# e202var-receiver-v1_1.net
KiCad netlist of a schematic drawn in EAGLE
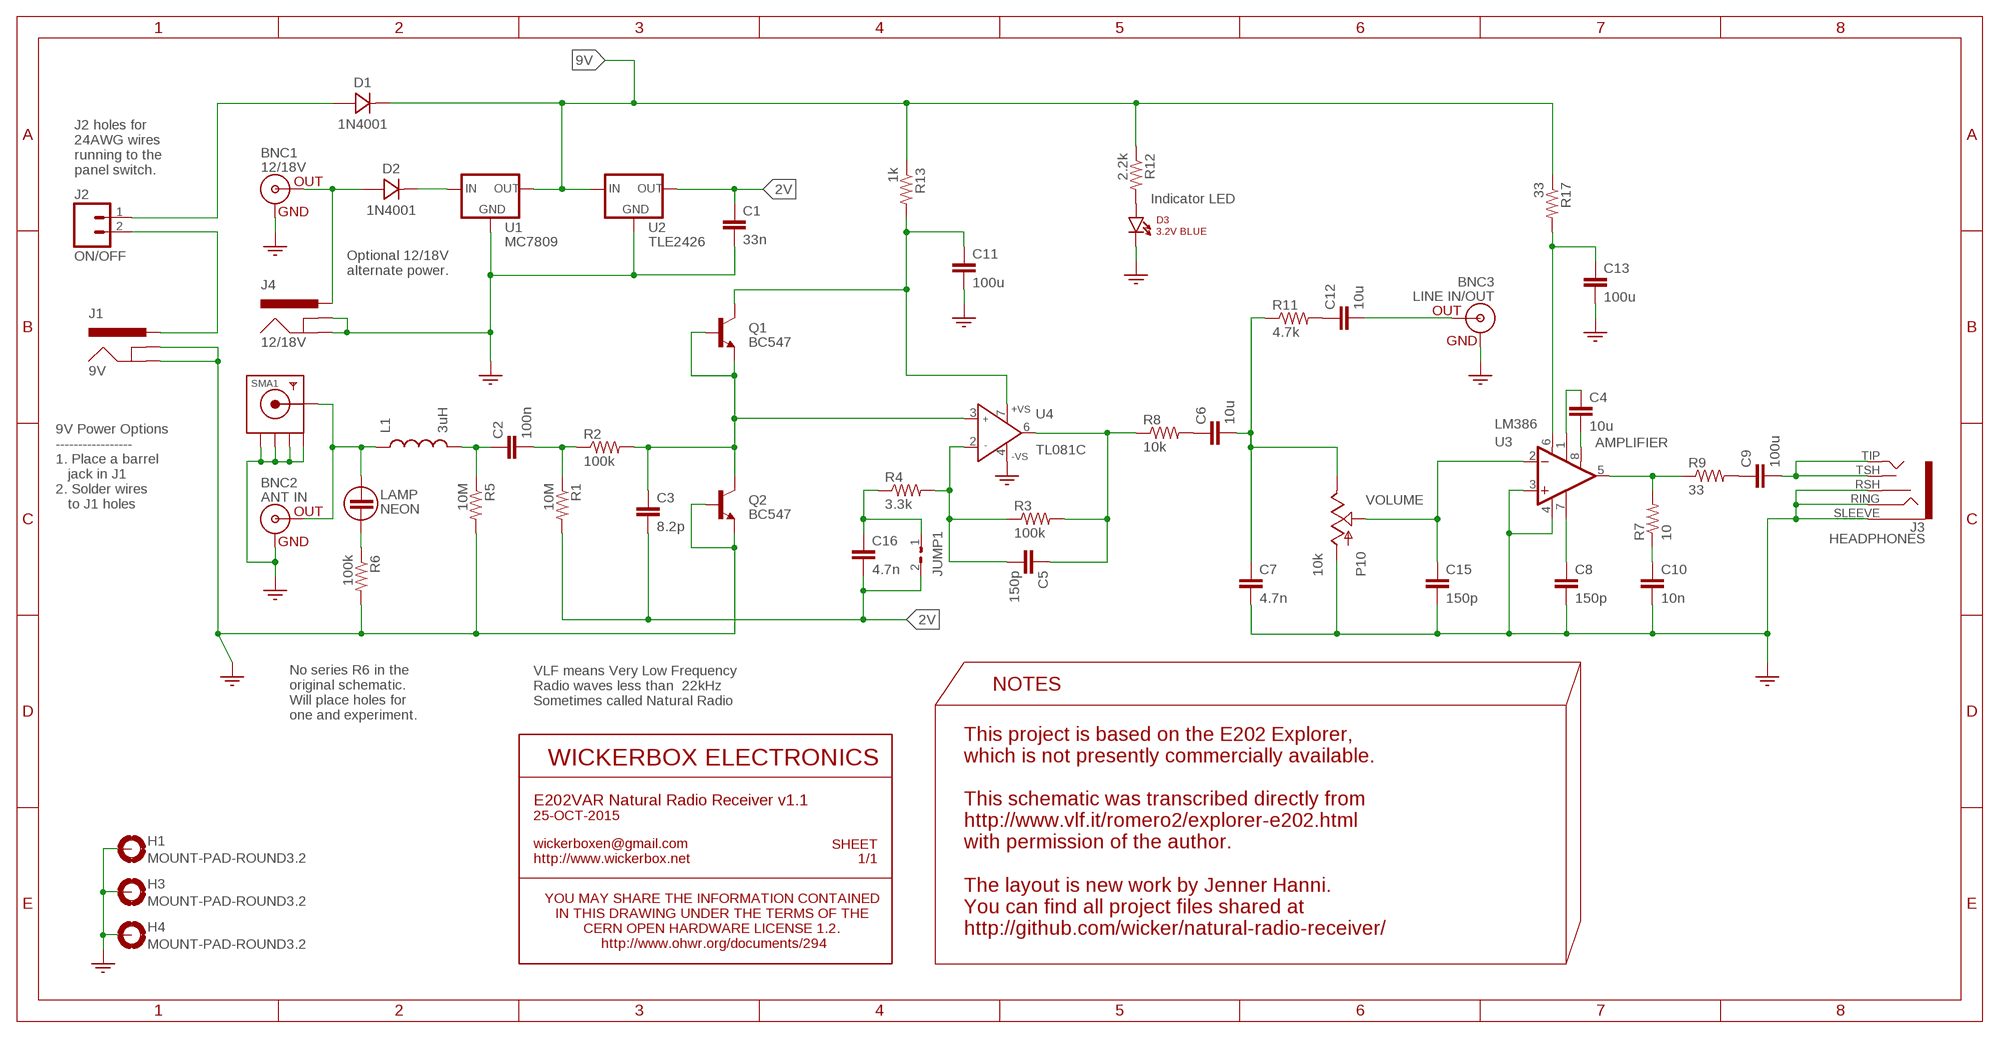
[diagram p0: schematic, sheet 1]

(export (version "E")
  (design (tool "Eeschema 10.0.6"))
  (components
    (comp (ref "BNC1")
      (value "12/18V")
      (footprint "eagle-import:BNC")
      (libsource (lib "eagle-import") (part "BNCPTH"))
    )
    (comp (ref "BNC2")
      (value "ANT IN")
      (footprint "eagle-import:BNC")
      (libsource (lib "eagle-import") (part "BNCPTH"))
    )
    (comp (ref "BNC3")
      (value "LINE IN/OUT")
      (footprint "eagle-import:BNC")
      (libsource (lib "eagle-import") (part "BNCPTH"))
    )
    (comp (ref "C1")
      (value "33n")
      (footprint "eagle-import:CAP-RADIAL-5MM-NONPOL")
      (libsource (lib "eagle-import") (part "CAPACITOR5MM"))
    )
    (comp (ref "C2")
      (value "100n")
      (footprint "eagle-import:CAP-RADIAL-5MM-NONPOL")
      (libsource (lib "eagle-import") (part "CAPACITOR5MM"))
    )
    (comp (ref "C3")
      (value "8.2p")
      (footprint "eagle-import:CAP-RADIAL-5MM-NONPOL")
      (libsource (lib "eagle-import") (part "CAPACITOR5MM"))
    )
    (comp (ref "C4")
      (value "10u")
      (footprint "eagle-import:CAP-RADIAL-2.5MM-NONPOL")
      (libsource (lib "eagle-import") (part "CAPACITOR2.5MM"))
    )
    (comp (ref "C5")
      (value "150p")
      (footprint "eagle-import:CAP-RADIAL-2.5MM-NONPOL")
      (libsource (lib "eagle-import") (part "CAPACITOR2.5MM"))
    )
    (comp (ref "C6")
      (value "10u")
      (footprint "eagle-import:CAP-RADIAL-2.5MM-NONPOL")
      (libsource (lib "eagle-import") (part "CAPACITOR2.5MM"))
    )
    (comp (ref "C7")
      (value "4.7n")
      (footprint "eagle-import:CAP-RADIAL-5MM-NONPOL")
      (libsource (lib "eagle-import") (part "CAPACITOR5MM"))
    )
    (comp (ref "C8")
      (value "150p")
      (footprint "eagle-import:CAP-RADIAL-2.5MM-NONPOL")
      (libsource (lib "eagle-import") (part "CAPACITOR2.5MM"))
    )
    (comp (ref "C9")
      (value "100u")
      (footprint "eagle-import:CAP-RADIAL-5MM-NONPOL")
      (libsource (lib "eagle-import") (part "CAPACITOR5MM"))
    )
    (comp (ref "C10")
      (value "10n")
      (footprint "eagle-import:CAP-RADIAL-2.5MM-NONPOL")
      (libsource (lib "eagle-import") (part "CAPACITOR2.5MM"))
    )
    (comp (ref "C11")
      (value "100u")
      (footprint "eagle-import:CAP-RADIAL-5MM-NONPOL")
      (libsource (lib "eagle-import") (part "CAPACITOR5MM"))
    )
    (comp (ref "C12")
      (value "10u")
      (footprint "eagle-import:CAP-RADIAL-2.5MM-NONPOL")
      (libsource (lib "eagle-import") (part "CAPACITOR2.5MM"))
    )
    (comp (ref "C13")
      (value "100u")
      (footprint "eagle-import:CAP-RADIAL-5MM-NONPOL")
      (libsource (lib "eagle-import") (part "CAPACITOR5MM"))
    )
    (comp (ref "C15")
      (value "150p")
      (footprint "eagle-import:CAP-RADIAL-2.5MM-NONPOL")
      (libsource (lib "eagle-import") (part "CAPACITOR2.5MM"))
    )
    (comp (ref "C16")
      (value "4.7n")
      (footprint "eagle-import:CAP-RADIAL-5MM-NONPOL")
      (libsource (lib "eagle-import") (part "CAPACITOR5MM"))
    )
    (comp (ref "D1")
      (value "1N4001")
      (footprint "eagle-import:DIODE-DO41")
      (libsource (lib "eagle-import") (part "DIODE"))
    )
    (comp (ref "D2")
      (value "1N4001")
      (footprint "eagle-import:DIODE-DO41")
      (libsource (lib "eagle-import") (part "DIODE"))
    )
    (comp (ref "D3")
      (value "3.2V BLUE")
      (footprint "eagle-import:LED-2PIN-0.1IN")
      (libsource (lib "eagle-import") (part "LED"))
    )
    (comp (ref "H1")
      (value "MOUNT-PAD-ROUND3.2")
      (footprint "eagle-import:3,2-PAD")
      (libsource (lib "eagle-import") (part "MOUNT-PAD-ROUND3.2"))
    )
    (comp (ref "H3")
      (value "MOUNT-PAD-ROUND3.2")
      (footprint "eagle-import:3,2-PAD")
      (libsource (lib "eagle-import") (part "MOUNT-PAD-ROUND3.2"))
    )
    (comp (ref "H4")
      (value "MOUNT-PAD-ROUND3.2")
      (footprint "eagle-import:3,2-PAD")
      (libsource (lib "eagle-import") (part "MOUNT-PAD-ROUND3.2"))
    )
    (comp (ref "J1")
      (value "9V")
      (footprint "eagle-import:JACK-POWER")
      (libsource (lib "eagle-import") (part "JACK-POWER-BARREL"))
    )
    (comp (ref "J2")
      (value "ON/OFF")
      (footprint "eagle-import:CONN-2PIN-0.1IN")
      (libsource (lib "eagle-import") (part "CONN-2PIN"))
    )
    (comp (ref "J3")
      (value "HEADPHONES")
      (footprint "eagle-import:JACK-AUDIO-5PIN")
      (libsource (lib "eagle-import") (part "JACK-AUDIO"))
    )
    (comp (ref "J4")
      (value "12/18V")
      (footprint "eagle-import:JACK-POWER")
      (libsource (lib "eagle-import") (part "JACK-POWER-BARREL"))
    )
    (comp (ref "JUMP1")
      (value "HPF")
      (footprint "eagle-import:CONN-2PIN-0.1IN")
      (libsource (lib "eagle-import") (part "JUMPER-SHUNT"))
    )
    (comp (ref "L1")
      (value "3uH")
      (footprint "eagle-import:RES-CF14-TH")
      (libsource (lib "eagle-import") (part "INDUCTOR"))
    )
    (comp (ref "LAMP")
      (value "NEON")
      (footprint "eagle-import:LAMP-2PIN-0.1IN")
      (libsource (lib "eagle-import") (part "LAMP-NEON"))
    )
    (comp (ref "P10")
      (value "10k")
      (footprint "eagle-import:POT-3PIN-LINEAR")
      (libsource (lib "eagle-import") (part "POT-P160KN-0QC15B10K"))
    )
    (comp (ref "Q1")
      (value "BC547")
      (footprint "eagle-import:TO-92-AMMO")
      (libsource (lib "eagle-import") (part "BJT-NPN"))
    )
    (comp (ref "Q2")
      (value "BC547")
      (footprint "eagle-import:TO-92-AMMO")
      (libsource (lib "eagle-import") (part "BJT-NPN"))
    )
    (comp (ref "R1")
      (value "10M")
      (footprint "eagle-import:RES-CF14-TH")
      (libsource (lib "eagle-import") (part "RESISTOR"))
    )
    (comp (ref "R2")
      (value "100k")
      (footprint "eagle-import:RES-CF14-TH")
      (libsource (lib "eagle-import") (part "RESISTOR"))
    )
    (comp (ref "R3")
      (value "100k")
      (footprint "eagle-import:RES-CF14-TH")
      (libsource (lib "eagle-import") (part "RESISTOR"))
    )
    (comp (ref "R4")
      (value "3.3k")
      (footprint "eagle-import:RES-CF14-TH")
      (libsource (lib "eagle-import") (part "RESISTOR"))
    )
    (comp (ref "R5")
      (value "10M")
      (footprint "eagle-import:RES-CF14-TH")
      (libsource (lib "eagle-import") (part "RESISTOR"))
    )
    (comp (ref "R6")
      (value "100k")
      (footprint "eagle-import:RES-CF14-TH")
      (libsource (lib "eagle-import") (part "RESISTOR"))
    )
    (comp (ref "R7")
      (value "10")
      (footprint "eagle-import:RES-CF14-TH")
      (libsource (lib "eagle-import") (part "RESISTOR"))
    )
    (comp (ref "R8")
      (value "10k")
      (footprint "eagle-import:RES-CF14-TH")
      (libsource (lib "eagle-import") (part "RESISTOR"))
    )
    (comp (ref "R9")
      (value "33")
      (footprint "eagle-import:RES-CF14-TH")
      (libsource (lib "eagle-import") (part "RESISTOR"))
    )
    (comp (ref "R11")
      (value "4.7k")
      (footprint "eagle-import:RES-CF14-TH")
      (libsource (lib "eagle-import") (part "RESISTOR"))
    )
    (comp (ref "R12")
      (value "2.2k")
      (footprint "eagle-import:RES-CF14-TH")
      (libsource (lib "eagle-import") (part "RESISTOR"))
    )
    (comp (ref "R13")
      (value "1k")
      (footprint "eagle-import:RES-CF14-TH")
      (libsource (lib "eagle-import") (part "RESISTOR"))
    )
    (comp (ref "R17")
      (value "33")
      (footprint "eagle-import:RES-CF14-TH")
      (libsource (lib "eagle-import") (part "RESISTOR"))
    )
    (comp (ref "SMA1")
      (value "SMACONNECTOR")
      (footprint "eagle-import:SMA90_DIP")
      (libsource (lib "eagle-import") (part "SMACONNECTOR"))
    )
    (comp (ref "U1")
      (value "MC7809")
      (footprint "eagle-import:TO-220")
      (libsource (lib "eagle-import") (part "VOLTREG-MC7809"))
    )
    (comp (ref "U2")
      (value "TLE2426")
      (footprint "eagle-import:DIP-08")
      (libsource (lib "eagle-import") (part "VOLTREG-TLE2426"))
    )
    (comp (ref "U3")
      (value "LM386")
      (footprint "eagle-import:DIP-08")
      (libsource (lib "eagle-import") (part "AMP-AUDIO-LM386"))
    )
    (comp (ref "U4")
      (value "TL081C")
      (footprint "eagle-import:DIP-08")
      (libsource (lib "eagle-import") (part "AMP-JFET-TL081CP"))
    )
  )
  (nets
    (net (code "1") (name "2V") (class "Default")
      (node (ref "C1") (pin "1") (pinfunction "1_1") (pintype "passive"))
      (node (ref "C16") (pin "2") (pinfunction "2_2") (pintype "passive"))
      (node (ref "C3") (pin "2") (pinfunction "2_2") (pintype "passive"))
      (node (ref "JUMP1") (pin "2") (pinfunction "2_2") (pintype "passive"))
      (node (ref "R1") (pin "P$2") (pinfunction "2_P$2") (pintype "passive"))
      (node (ref "U2") (pin "1") (pinfunction "OUT_1") (pintype "output"))
    )
    (net (code "2") (name "9V") (class "Default")
      (node (ref "D1") (pin "C") (pinfunction "CATHODE_C") (pintype "passive"))
      (node (ref "R12") (pin "P$1") (pinfunction "1_P$1") (pintype "passive"))
      (node (ref "R13") (pin "P$1") (pinfunction "1_P$1") (pintype "passive"))
      (node (ref "R17") (pin "P$1") (pinfunction "1_P$1") (pintype "passive"))
      (node (ref "U1") (pin "OUT") (pinfunction "OUT_OUT") (pintype "output"))
      (node (ref "U2") (pin "3") (pinfunction "IN_3") (pintype "input"))
    )
    (net (code "3") (name "GND") (class "Default")
      (node (ref "BNC1") (pin "GND") (pinfunction "GND_GND") (pintype "bidirectional"))
      (node (ref "BNC2") (pin "GND") (pinfunction "GND_GND") (pintype "bidirectional"))
      (node (ref "BNC3") (pin "GND") (pinfunction "GND_GND") (pintype "bidirectional"))
      (node (ref "C1") (pin "2") (pinfunction "2_2") (pintype "passive"))
      (node (ref "C10") (pin "2") (pinfunction "2_2") (pintype "passive"))
      (node (ref "C11") (pin "2") (pinfunction "2_2") (pintype "passive"))
      (node (ref "C13") (pin "2") (pinfunction "2_2") (pintype "passive"))
      (node (ref "C15") (pin "2") (pinfunction "2_2") (pintype "passive"))
      (node (ref "C7") (pin "2") (pinfunction "2_2") (pintype "passive"))
      (node (ref "C8") (pin "2") (pinfunction "2_2") (pintype "passive"))
      (node (ref "D3") (pin "C") (pinfunction "CATHODE_C") (pintype "bidirectional"))
      (node (ref "H1") (pin "B3,2") (pinfunction "MOUNT_B3,2") (pintype "passive"))
      (node (ref "H3") (pin "B3,2") (pinfunction "MOUNT_B3,2") (pintype "passive"))
      (node (ref "H4") (pin "B3,2") (pinfunction "MOUNT_B3,2") (pintype "passive"))
      (node (ref "J1") (pin "GND") (pinfunction "GND_GND") (pintype "bidirectional"))
      (node (ref "J1") (pin "GNDBREAK") (pinfunction "GNDBREAK_GNDBREAK") (pintype "bidirectional"))
      (node (ref "J3") (pin "RING") (pinfunction "RING_RING") (pintype "bidirectional"))
      (node (ref "J3") (pin "RSH") (pinfunction "RSH_RSH") (pintype "bidirectional"))
      (node (ref "J3") (pin "SLEEVE") (pinfunction "SLEEVE_SLEEVE") (pintype "bidirectional"))
      (node (ref "J4") (pin "GND") (pinfunction "GND_GND") (pintype "bidirectional"))
      (node (ref "J4") (pin "GNDBREAK") (pinfunction "GNDBREAK_GNDBREAK") (pintype "bidirectional"))
      (node (ref "P10") (pin "1") (pinfunction "A_1") (pintype "passive"))
      (node (ref "Q2") (pin "2") (pinfunction "B_2") (pintype "passive"))
      (node (ref "Q2") (pin "3") (pinfunction "E_3") (pintype "passive"))
      (node (ref "R5") (pin "P$2") (pinfunction "2_P$2") (pintype "passive"))
      (node (ref "R6") (pin "P$2") (pinfunction "2_P$2") (pintype "passive"))
      (node (ref "SMA1") (pin "GND1") (pinfunction "GND1_GND1") (pintype "power_in"))
      (node (ref "SMA1") (pin "GND2") (pinfunction "GND2_GND2") (pintype "power_in"))
      (node (ref "SMA1") (pin "GND3") (pinfunction "GND3_GND3") (pintype "power_in"))
      (node (ref "SMA1") (pin "GND4") (pinfunction "GND4_GND4") (pintype "power_in"))
      (node (ref "U1") (pin "GND") (pinfunction "GND_GND") (pintype "input"))
      (node (ref "U2") (pin "2") (pinfunction "GND_2") (pintype "input"))
      (node (ref "U3") (pin "3") (pinfunction "+IN_3") (pintype "input"))
      (node (ref "U3") (pin "4") (pinfunction "V-_4") (pintype "power_in"))
      (node (ref "U4") (pin "4") (pinfunction "-VS_4") (pintype "input"))
    )
    (net (code "4") (name "Net-(BNC1-OUT)") (class "Default")
      (node (ref "BNC1") (pin "S") (pinfunction "OUT_S") (pintype "bidirectional"))
      (node (ref "D2") (pin "A") (pinfunction "ANODE_A") (pintype "passive"))
      (node (ref "J4") (pin "PWR") (pinfunction "PWR_PWR") (pintype "bidirectional"))
    )
    (net (code "5") (name "Net-(BNC2-OUT)") (class "Default")
      (node (ref "BNC2") (pin "S") (pinfunction "OUT_S") (pintype "bidirectional"))
      (node (ref "L1") (pin "P$1") (pinfunction "1_P$1") (pintype "passive"))
      (node (ref "LAMP") (pin "A") (pinfunction "1_A") (pintype "passive"))
      (node (ref "SMA1") (pin "ANTENNA") (pinfunction "ANT_ANTENNA") (pintype "bidirectional"))
    )
    (net (code "6") (name "Net-(BNC3-OUT)") (class "Default")
      (node (ref "BNC3") (pin "S") (pinfunction "OUT_S") (pintype "bidirectional"))
      (node (ref "C12") (pin "2") (pinfunction "2_2") (pintype "passive"))
    )
    (net (code "7") (name "Net-(C4-Pad1)") (class "Default")
      (node (ref "C4") (pin "1") (pinfunction "1_1") (pintype "passive"))
      (node (ref "U3") (pin "1") (pinfunction "GAIN_1") (pintype "bidirectional"))
    )
    (net (code "8") (name "Net-(C4-Pad2)") (class "Default")
      (node (ref "C4") (pin "2") (pinfunction "2_2") (pintype "passive"))
      (node (ref "U3") (pin "8") (pinfunction "GAIN_8") (pintype "bidirectional"))
    )
    (net (code "9") (name "Net-(C9-Pad2)") (class "Default")
      (node (ref "C9") (pin "2") (pinfunction "2_2") (pintype "passive"))
      (node (ref "J3") (pin "TIP") (pinfunction "TIP_TIP") (pintype "bidirectional"))
      (node (ref "J3") (pin "TSH") (pinfunction "TSH_TSH") (pintype "bidirectional"))
    )
    (net (code "10") (name "Net-(D1-ANODE)") (class "Default")
      (node (ref "D1") (pin "A") (pinfunction "ANODE_A") (pintype "passive"))
      (node (ref "J2") (pin "1") (pinfunction "1_1") (pintype "passive"))
    )
    (net (code "11") (name "Net-(D2-CATHODE)") (class "Default")
      (node (ref "D2") (pin "C") (pinfunction "CATHODE_C") (pintype "passive"))
      (node (ref "U1") (pin "IN") (pinfunction "IN_IN") (pintype "input"))
    )
    (net (code "12") (name "Net-(D3-ANODE)") (class "Default")
      (node (ref "D3") (pin "A") (pinfunction "ANODE_A") (pintype "bidirectional"))
      (node (ref "R12") (pin "P$2") (pinfunction "2_P$2") (pintype "passive"))
    )
    (net (code "13") (name "Net-(J1-PadPWR)") (class "Default")
      (node (ref "J1") (pin "PWR") (pinfunction "PWR_PWR") (pintype "bidirectional"))
      (node (ref "J2") (pin "2") (pinfunction "2_2") (pintype "passive"))
    )
    (net (code "14") (name "Net-(L1-2)") (class "Default")
      (node (ref "C2") (pin "1") (pinfunction "1_1") (pintype "passive"))
      (node (ref "L1") (pin "P$2") (pinfunction "2_P$2") (pintype "passive"))
      (node (ref "R5") (pin "P$1") (pinfunction "1_P$1") (pintype "passive"))
    )
    (net (code "15") (name "Net-(LAMP-2)") (class "Default")
      (node (ref "LAMP") (pin "C") (pinfunction "2_C") (pintype "passive"))
      (node (ref "R6") (pin "P$1") (pinfunction "1_P$1") (pintype "passive"))
    )
    (net (code "16") (name "Net-(P10-E)") (class "Default")
      (node (ref "C6") (pin "2") (pinfunction "2_2") (pintype "passive"))
      (node (ref "C7") (pin "1") (pinfunction "1_1") (pintype "passive"))
      (node (ref "P10") (pin "3") (pinfunction "E_3") (pintype "passive"))
      (node (ref "R11") (pin "P$1") (pinfunction "1_P$1") (pintype "passive"))
    )
    (net (code "17") (name "Net-(P10-S)") (class "Default")
      (node (ref "C15") (pin "1") (pinfunction "1_1") (pintype "passive"))
      (node (ref "P10") (pin "2") (pinfunction "S_2") (pintype "passive"))
      (node (ref "U3") (pin "2") (pinfunction "-IN_2") (pintype "input"))
    )
    (net (code "18") (name "Net-(Q1-B)") (class "Default")
      (node (ref "C3") (pin "1") (pinfunction "1_1") (pintype "passive"))
      (node (ref "Q1") (pin "2") (pinfunction "B_2") (pintype "passive"))
      (node (ref "Q1") (pin "3") (pinfunction "E_3") (pintype "passive"))
      (node (ref "Q2") (pin "1") (pinfunction "C_1") (pintype "passive"))
      (node (ref "R2") (pin "P$2") (pinfunction "2_P$2") (pintype "passive"))
      (node (ref "U4") (pin "3") (pinfunction "IN+_3") (pintype "input"))
    )
    (net (code "19") (name "Net-(Q1-C)") (class "Default")
      (node (ref "C11") (pin "1") (pinfunction "1_1") (pintype "passive"))
      (node (ref "Q1") (pin "1") (pinfunction "C_1") (pintype "passive"))
      (node (ref "R13") (pin "P$2") (pinfunction "2_P$2") (pintype "passive"))
      (node (ref "U4") (pin "7") (pinfunction "+VS_7") (pintype "input"))
    )
    (net (code "20") (name "Net-(R1-1)") (class "Default")
      (node (ref "C2") (pin "2") (pinfunction "2_2") (pintype "passive"))
      (node (ref "R1") (pin "P$1") (pinfunction "1_P$1") (pintype "passive"))
      (node (ref "R2") (pin "P$1") (pinfunction "1_P$1") (pintype "passive"))
    )
    (net (code "21") (name "Net-(R3-1)") (class "Default")
      (node (ref "C5") (pin "2") (pinfunction "2_2") (pintype "passive"))
      (node (ref "R3") (pin "P$1") (pinfunction "1_P$1") (pintype "passive"))
      (node (ref "R4") (pin "P$2") (pinfunction "2_P$2") (pintype "passive"))
      (node (ref "U4") (pin "2") (pinfunction "IN-_2") (pintype "input"))
    )
    (net (code "22") (name "Net-(R3-2)") (class "Default")
      (node (ref "C5") (pin "1") (pinfunction "1_1") (pintype "passive"))
      (node (ref "R3") (pin "P$2") (pinfunction "2_P$2") (pintype "passive"))
      (node (ref "R8") (pin "P$1") (pinfunction "1_P$1") (pintype "passive"))
      (node (ref "U4") (pin "6") (pinfunction "OUT_6") (pintype "output"))
    )
    (net (code "23") (name "Net-(R4-1)") (class "Default")
      (node (ref "C16") (pin "1") (pinfunction "1_1") (pintype "passive"))
      (node (ref "JUMP1") (pin "1") (pinfunction "1_1") (pintype "passive"))
      (node (ref "R4") (pin "P$1") (pinfunction "1_P$1") (pintype "passive"))
    )
    (net (code "24") (name "Net-(R7-1)") (class "Default")
      (node (ref "C10") (pin "1") (pinfunction "1_1") (pintype "passive"))
      (node (ref "R7") (pin "P$1") (pinfunction "1_P$1") (pintype "passive"))
    )
    (net (code "25") (name "Net-(R7-2)") (class "Default")
      (node (ref "R7") (pin "P$2") (pinfunction "2_P$2") (pintype "passive"))
      (node (ref "R9") (pin "P$1") (pinfunction "1_P$1") (pintype "passive"))
      (node (ref "U3") (pin "5") (pinfunction "OUT_5") (pintype "output"))
    )
    (net (code "26") (name "Net-(R8-2)") (class "Default")
      (node (ref "C6") (pin "1") (pinfunction "1_1") (pintype "passive"))
      (node (ref "R8") (pin "P$2") (pinfunction "2_P$2") (pintype "passive"))
    )
    (net (code "27") (name "Net-(R9-2)") (class "Default")
      (node (ref "C9") (pin "1") (pinfunction "1_1") (pintype "passive"))
      (node (ref "R9") (pin "P$2") (pinfunction "2_P$2") (pintype "passive"))
    )
    (net (code "28") (name "Net-(R11-2)") (class "Default")
      (node (ref "C12") (pin "1") (pinfunction "1_1") (pintype "passive"))
      (node (ref "R11") (pin "P$2") (pinfunction "2_P$2") (pintype "passive"))
    )
    (net (code "29") (name "Net-(R17-2)") (class "Default")
      (node (ref "C13") (pin "1") (pinfunction "1_1") (pintype "passive"))
      (node (ref "R17") (pin "P$2") (pinfunction "2_P$2") (pintype "passive"))
      (node (ref "U3") (pin "6") (pinfunction "V+_6") (pintype "power_in"))
    )
    (net (code "30") (name "Net-(U3-BP)") (class "Default")
      (node (ref "C8") (pin "1") (pinfunction "1_1") (pintype "passive"))
      (node (ref "U3") (pin "7") (pinfunction "BP_7") (pintype "bidirectional"))
    )
  )
)
